# tractor_1v2.net
KiCad netlist of a schematic drawn in EAGLE
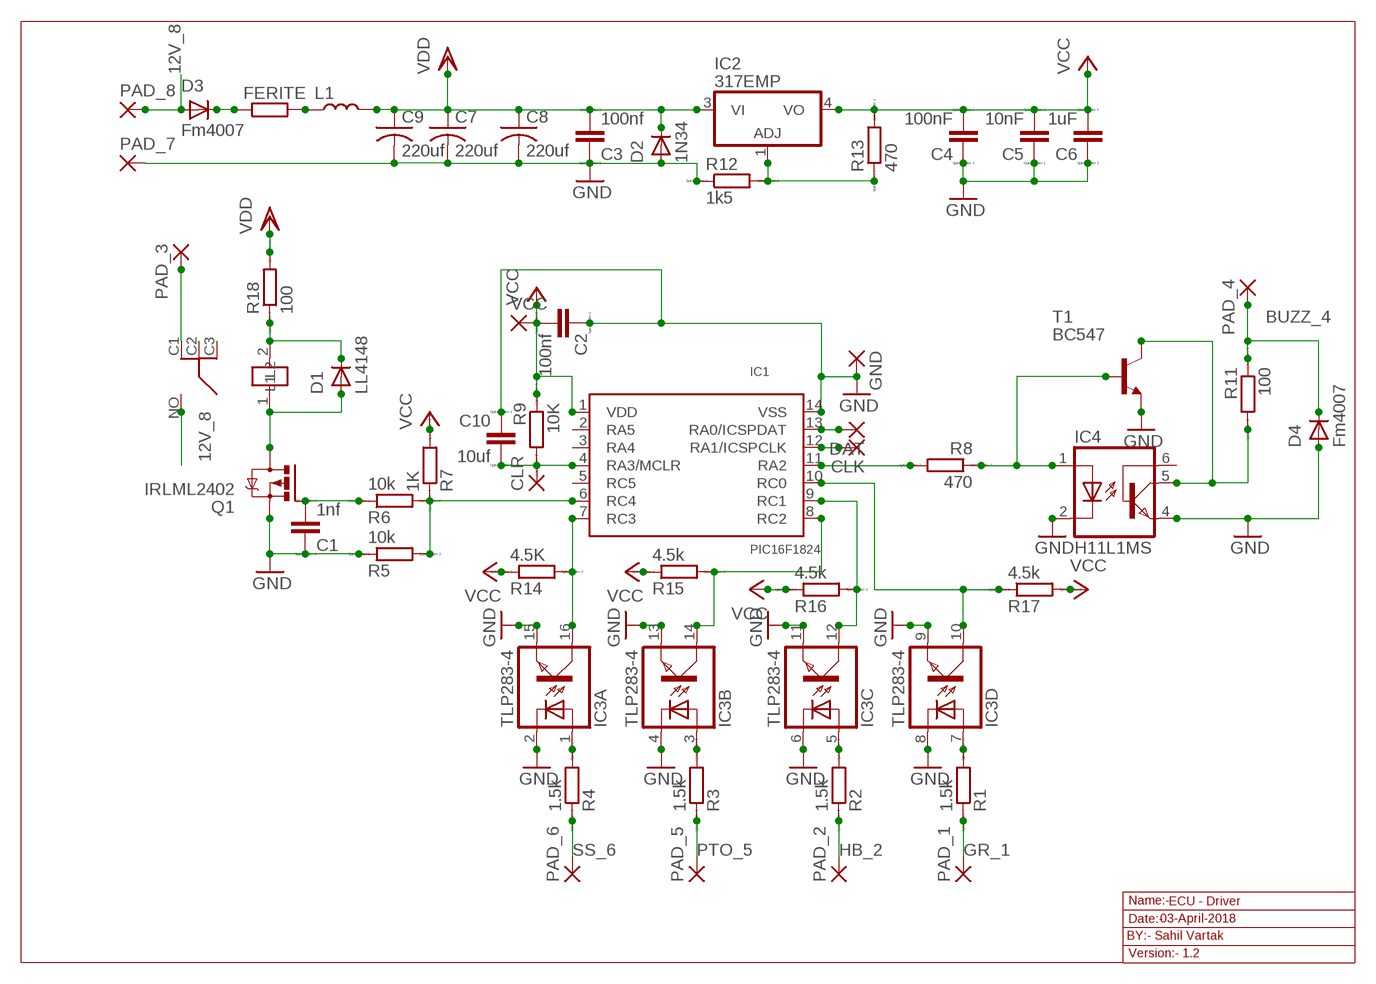
[diagram p0: schematic, sheet 1]

(export (version "E")
  (design (tool "Eeschema 10.0.6"))
  (components
    (comp (ref "C1")
      (value "1nf")
      (footprint "eagle-import:C0603")
      (libsource (lib "eagle-import") (part "CC0603"))
    )
    (comp (ref "C2")
      (value "100nf")
      (footprint "eagle-import:C0603")
      (libsource (lib "eagle-import") (part "CC0603"))
    )
    (comp (ref "C3")
      (value "100nf")
      (footprint "eagle-import:C0603")
      (libsource (lib "eagle-import") (part "CC0603"))
    )
    (comp (ref "C4")
      (value "100nF")
      (footprint "eagle-import:C0603")
      (libsource (lib "eagle-import") (part "CC0603"))
    )
    (comp (ref "C5")
      (value "10nF")
      (footprint "eagle-import:C0603")
      (libsource (lib "eagle-import") (part "CC0603"))
    )
    (comp (ref "C6")
      (value "1uF")
      (footprint "eagle-import:C0603")
      (libsource (lib "eagle-import") (part "CC0603"))
    )
    (comp (ref "C7")
      (value "220uf")
      (footprint "eagle-import:C025-025X050")
      (libsource (lib "eagle-import") (part "C-US025-025X050"))
    )
    (comp (ref "C8")
      (value "220uf")
      (footprint "eagle-import:C025-025X050")
      (libsource (lib "eagle-import") (part "C-US025-025X050"))
    )
    (comp (ref "C9")
      (value "220uf")
      (footprint "eagle-import:C025-025X050")
      (libsource (lib "eagle-import") (part "C-US025-025X050"))
    )
    (comp (ref "C10")
      (value "10uf")
      (footprint "eagle-import:C0603")
      (libsource (lib "eagle-import") (part "CC0603"))
    )
    (comp (ref "CLK")
      (value "1,6/0,8")
      (footprint "eagle-import:1,6_0,8")
      (libsource (lib "eagle-import") (part "1,6/0,8"))
    )
    (comp (ref "CLR")
      (value "1,6/0,8")
      (footprint "eagle-import:1,6_0,8")
      (libsource (lib "eagle-import") (part "1,6/0,8"))
    )
    (comp (ref "D1")
      (value "LL4148")
      (footprint "eagle-import:SMA-DO214AC")
      (libsource (lib "eagle-import") (part "GF1"))
    )
    (comp (ref "D2")
      (value "1N34")
      (footprint "eagle-import:SMA-DO214AC")
      (libsource (lib "eagle-import") (part "GF1"))
    )
    (comp (ref "D3")
      (value "Fm4007")
      (footprint "eagle-import:SMA-DO214AC")
      (libsource (lib "eagle-import") (part "GF1"))
    )
    (comp (ref "D4")
      (value "Fm4007")
      (footprint "eagle-import:SMA-DO214AC")
      (libsource (lib "eagle-import") (part "GF1"))
    )
    (comp (ref "DAT")
      (value "1,6/0,8")
      (footprint "eagle-import:1,6_0,8")
      (libsource (lib "eagle-import") (part "1,6/0,8"))
    )
    (comp (ref "FERITE")
      (value "R-EU_R0603")
      (footprint "eagle-import:R0603")
      (libsource (lib "eagle-import") (part "R-EU_R0603"))
    )
    (comp (ref "GND")
      (value "1,6/0,8")
      (footprint "eagle-import:1,6_0,8")
      (libsource (lib "eagle-import") (part "1,6/0,8"))
    )
    (comp (ref "IC1")
      (value "PIC16F1824")
      (footprint "eagle-import:SO-14")
      (libsource (lib "eagle-import") (part "PIC16F1824"))
    )
    (comp (ref "IC2")
      (value "317EMP")
      (footprint "eagle-import:SOT223")
      (libsource (lib "eagle-import") (part "317EMP"))
    )
    (comp (ref "IC3")
      (value "TLP283-4")
      (footprint "eagle-import:MINI-FLAT-16")
      (libsource (lib "eagle-import") (part "TLP283-4"))
    )
    (comp (ref "IC4")
      (value "H11L1MS")
      (footprint "eagle-import:DIL6-SMD")
      (libsource (lib "eagle-import") (part "H11LMS1"))
    )
    (comp (ref "K2")
      (value "RL703")
      (footprint "eagle-import:RL703")
      (libsource (lib "eagle-import") (part "RL703"))
    )
    (comp (ref "L1")
      (value "R-US_WSC2515")
      (footprint "eagle-import:WSC2515")
      (libsource (lib "eagle-import") (part "R-US_WSC2515"))
    )
    (comp (ref "PAD_1")
      (value "2,54/1,1")
      (footprint "eagle-import:2,54_1,1")
      (libsource (lib "eagle-import") (part "2,54/1,1"))
    )
    (comp (ref "PAD_2")
      (value "2,54/1,1")
      (footprint "eagle-import:2,54_1,1")
      (libsource (lib "eagle-import") (part "2,54/1,1"))
    )
    (comp (ref "PAD_3")
      (value "2,54/1,1")
      (footprint "eagle-import:2,54_1,1")
      (libsource (lib "eagle-import") (part "2,54/1,1"))
    )
    (comp (ref "PAD_4")
      (value "2,54/1,1")
      (footprint "eagle-import:2,54_1,1")
      (libsource (lib "eagle-import") (part "2,54/1,1"))
    )
    (comp (ref "PAD_5")
      (value "2,54/1,1")
      (footprint "eagle-import:2,54_1,1")
      (libsource (lib "eagle-import") (part "2,54/1,1"))
    )
    (comp (ref "PAD_6")
      (value "2,54/1,1")
      (footprint "eagle-import:2,54_1,1")
      (libsource (lib "eagle-import") (part "2,54/1,1"))
    )
    (comp (ref "PAD_7")
      (value "2,54/1,1")
      (footprint "eagle-import:2,54_1,1")
      (libsource (lib "eagle-import") (part "2,54/1,1"))
    )
    (comp (ref "PAD_8")
      (value "2,54/1,1")
      (footprint "eagle-import:2,54_1,1")
      (libsource (lib "eagle-import") (part "2,54/1,1"))
    )
    (comp (ref "Q1")
      (value "IRLML2402")
      (footprint "eagle-import:MICRO3")
      (libsource (lib "eagle-import") (part "IRLML5203"))
    )
    (comp (ref "R1")
      (value "1.5k")
      (footprint "eagle-import:R0603")
      (libsource (lib "eagle-import") (part "RR0603"))
    )
    (comp (ref "R2")
      (value "1.5k")
      (footprint "eagle-import:R0603")
      (libsource (lib "eagle-import") (part "RR0603"))
    )
    (comp (ref "R3")
      (value "1.5k")
      (footprint "eagle-import:R0603")
      (libsource (lib "eagle-import") (part "RR0603"))
    )
    (comp (ref "R4")
      (value "1.5k")
      (footprint "eagle-import:R0603")
      (libsource (lib "eagle-import") (part "RR0603"))
    )
    (comp (ref "R5")
      (value "10k")
      (footprint "eagle-import:R0603")
      (libsource (lib "eagle-import") (part "RR0603"))
    )
    (comp (ref "R6")
      (value "10k")
      (footprint "eagle-import:R0603")
      (libsource (lib "eagle-import") (part "RR0603"))
    )
    (comp (ref "R7")
      (value "1K")
      (footprint "eagle-import:R0603")
      (libsource (lib "eagle-import") (part "RR0603"))
    )
    (comp (ref "R8")
      (value "470")
      (footprint "eagle-import:R0603")
      (libsource (lib "eagle-import") (part "RR0603"))
    )
    (comp (ref "R9")
      (value "10K")
      (footprint "eagle-import:R0603")
      (libsource (lib "eagle-import") (part "RR0603"))
    )
    (comp (ref "R11")
      (value "100")
      (footprint "eagle-import:R0603")
      (libsource (lib "eagle-import") (part "RR0603"))
    )
    (comp (ref "R12")
      (value "1k5")
      (footprint "eagle-import:R0603")
      (libsource (lib "eagle-import") (part "RR0603"))
    )
    (comp (ref "R13")
      (value "470")
      (footprint "eagle-import:R0603")
      (libsource (lib "eagle-import") (part "RR0603"))
    )
    (comp (ref "R14")
      (value "4.5K")
      (footprint "eagle-import:R0603")
      (libsource (lib "eagle-import") (part "RR0603"))
    )
    (comp (ref "R15")
      (value "4.5k")
      (footprint "eagle-import:R0603")
      (libsource (lib "eagle-import") (part "RR0603"))
    )
    (comp (ref "R16")
      (value "4.5k")
      (footprint "eagle-import:R0603")
      (libsource (lib "eagle-import") (part "RR0603"))
    )
    (comp (ref "R17")
      (value "4.5k")
      (footprint "eagle-import:R0603")
      (libsource (lib "eagle-import") (part "RR0603"))
    )
    (comp (ref "R18")
      (value "100")
      (footprint "eagle-import:R0603")
      (libsource (lib "eagle-import") (part "RR0603"))
    )
    (comp (ref "T1")
      (value "BC547")
      (footprint "eagle-import:TO92")
      (libsource (lib "eagle-import") (part "BC547"))
    )
    (comp (ref "VCC")
      (value "1,6/0,8")
      (footprint "eagle-import:1,6_0,8")
      (libsource (lib "eagle-import") (part "1,6/0,8"))
    )
  )
  (nets
    (net (code "1") (name "/12V_8") (class "Default")
      (node (ref "D3") (pin "A") (pinfunction "A_A") (pintype "passive"))
      (node (ref "K2") (pin "NO") (pinfunction "NO_NO") (pintype "bidirectional"))
      (node (ref "PAD_8") (pin "1") (pinfunction "P_1") (pintype "passive"))
    )
    (net (code "2") (name "/BUZZ_4") (class "Default")
      (node (ref "D4") (pin "K") (pinfunction "C_K") (pintype "passive"))
      (node (ref "PAD_4") (pin "1") (pinfunction "P_1") (pintype "passive"))
      (node (ref "R11") (pin "1") (pinfunction "1_1") (pintype "passive"))
    )
    (net (code "3") (name "/GR_1") (class "Default")
      (node (ref "PAD_1") (pin "1") (pinfunction "P_1") (pintype "passive"))
      (node (ref "R1") (pin "1") (pinfunction "1_1") (pintype "passive"))
    )
    (net (code "4") (name "/HB_2") (class "Default")
      (node (ref "PAD_2") (pin "1") (pinfunction "P_1") (pintype "passive"))
      (node (ref "R2") (pin "1") (pinfunction "1_1") (pintype "passive"))
    )
    (net (code "5") (name "/PTO_5") (class "Default")
      (node (ref "PAD_5") (pin "1") (pinfunction "P_1") (pintype "passive"))
      (node (ref "R3") (pin "1") (pinfunction "1_1") (pintype "passive"))
    )
    (net (code "6") (name "/SS_6") (class "Default")
      (node (ref "PAD_6") (pin "1") (pinfunction "P_1") (pintype "passive"))
      (node (ref "R4") (pin "1") (pinfunction "1_1") (pintype "passive"))
    )
    (net (code "7") (name "GND") (class "Default")
      (node (ref "C1") (pin "1") (pinfunction "1_1") (pintype "passive"))
      (node (ref "C10") (pin "1") (pinfunction "1_1") (pintype "passive"))
      (node (ref "C2") (pin "1") (pinfunction "1_1") (pintype "passive"))
      (node (ref "C3") (pin "1") (pinfunction "1_1") (pintype "passive"))
      (node (ref "C4") (pin "1") (pinfunction "1_1") (pintype "passive"))
      (node (ref "C5") (pin "1") (pinfunction "1_1") (pintype "passive"))
      (node (ref "C6") (pin "1") (pinfunction "1_1") (pintype "passive"))
      (node (ref "C7") (pin "2") (pinfunction "2_2") (pintype "passive"))
      (node (ref "C8") (pin "2") (pinfunction "2_2") (pintype "passive"))
      (node (ref "C9") (pin "2") (pinfunction "2_2") (pintype "passive"))
      (node (ref "D2") (pin "A") (pinfunction "A_A") (pintype "passive"))
      (node (ref "D4") (pin "A") (pinfunction "A_A") (pintype "passive"))
      (node (ref "GND") (pin "1") (pinfunction "P_1") (pintype "passive"))
      (node (ref "IC1") (pin "14") (pinfunction "VSS_14") (pintype "bidirectional"))
      (node (ref "IC3") (pin "11") (pinfunction "EMIT_11") (pintype "passive"))
      (node (ref "IC3") (pin "13") (pinfunction "EMIT_13") (pintype "passive"))
      (node (ref "IC3") (pin "15") (pinfunction "EMIT_15") (pintype "passive"))
      (node (ref "IC3") (pin "2") (pinfunction "C_2") (pintype "passive"))
      (node (ref "IC3") (pin "4") (pinfunction "C_4") (pintype "passive"))
      (node (ref "IC3") (pin "6") (pinfunction "C_6") (pintype "passive"))
      (node (ref "IC3") (pin "8") (pinfunction "C_8") (pintype "passive"))
      (node (ref "IC3") (pin "9") (pinfunction "EMIT_9") (pintype "passive"))
      (node (ref "IC4") (pin "2") (pinfunction "C_2") (pintype "passive"))
      (node (ref "IC4") (pin "4") (pinfunction "EMI_4") (pintype "passive"))
      (node (ref "PAD_7") (pin "1") (pinfunction "P_1") (pintype "passive"))
      (node (ref "Q1") (pin "2") (pinfunction "S_2") (pintype "passive"))
      (node (ref "R12") (pin "1") (pinfunction "1_1") (pintype "passive"))
      (node (ref "R5") (pin "1") (pinfunction "1_1") (pintype "passive"))
      (node (ref "T1") (pin "1") (pinfunction "E_1") (pintype "passive"))
    )
    (net (code "8") (name "Net-(CLK-P)") (class "Default")
      (node (ref "CLK") (pin "1") (pinfunction "P_1") (pintype "passive"))
      (node (ref "IC1") (pin "12") (pinfunction "RA1/ICSPCLK_12") (pintype "bidirectional"))
    )
    (net (code "9") (name "Net-(CLR-P)") (class "Default")
      (node (ref "C10") (pin "2") (pinfunction "2_2") (pintype "passive"))
      (node (ref "CLR") (pin "1") (pinfunction "P_1") (pintype "passive"))
      (node (ref "IC1") (pin "4") (pinfunction "RA3/MCLR_4") (pintype "bidirectional"))
      (node (ref "R9") (pin "2") (pinfunction "2_2") (pintype "passive"))
    )
    (net (code "10") (name "Net-(D1-C)") (class "Default")
      (node (ref "D1") (pin "K") (pinfunction "C_K") (pintype "passive"))
      (node (ref "K2") (pin "2") (pinfunction "L1_2") (pintype "bidirectional"))
      (node (ref "R18") (pin "1") (pinfunction "1_1") (pintype "passive"))
    )
    (net (code "11") (name "Net-(D3-C)") (class "Default")
      (node (ref "D3") (pin "K") (pinfunction "C_K") (pintype "passive"))
      (node (ref "FERITE") (pin "1") (pinfunction "1_1") (pintype "passive"))
    )
    (net (code "12") (name "Net-(DAT-P)") (class "Default")
      (node (ref "DAT") (pin "1") (pinfunction "P_1") (pintype "passive"))
      (node (ref "IC1") (pin "13") (pinfunction "RA0/ICSPDAT_13") (pintype "bidirectional"))
    )
    (net (code "13") (name "Net-(FERITE-Pad2)") (class "Default")
      (node (ref "FERITE") (pin "2") (pinfunction "2_2") (pintype "passive"))
      (node (ref "L1") (pin "1") (pinfunction "1_1") (pintype "passive"))
    )
    (net (code "14") (name "Net-(IC1-RA2)") (class "Default")
      (node (ref "IC1") (pin "11") (pinfunction "RA2_11") (pintype "bidirectional"))
      (node (ref "R8") (pin "2") (pinfunction "2_2") (pintype "passive"))
    )
    (net (code "15") (name "Net-(IC1-RC0)") (class "Default")
      (node (ref "IC1") (pin "10") (pinfunction "RC0_10") (pintype "bidirectional"))
      (node (ref "IC3") (pin "10") (pinfunction "COL_10") (pintype "passive"))
      (node (ref "R17") (pin "1") (pinfunction "1_1") (pintype "passive"))
    )
    (net (code "16") (name "Net-(IC1-RC1)") (class "Default")
      (node (ref "IC1") (pin "9") (pinfunction "RC1_9") (pintype "bidirectional"))
      (node (ref "IC3") (pin "12") (pinfunction "COL_12") (pintype "passive"))
      (node (ref "R16") (pin "2") (pinfunction "2_2") (pintype "passive"))
    )
    (net (code "17") (name "Net-(IC1-RC2)") (class "Default")
      (node (ref "IC1") (pin "8") (pinfunction "RC2_8") (pintype "bidirectional"))
      (node (ref "IC3") (pin "14") (pinfunction "COL_14") (pintype "passive"))
      (node (ref "R15") (pin "2") (pinfunction "2_2") (pintype "passive"))
    )
    (net (code "18") (name "Net-(IC1-RC3)") (class "Default")
      (node (ref "IC1") (pin "7") (pinfunction "RC3_7") (pintype "bidirectional"))
      (node (ref "IC3") (pin "16") (pinfunction "COL_16") (pintype "passive"))
      (node (ref "R14") (pin "2") (pinfunction "2_2") (pintype "passive"))
    )
    (net (code "19") (name "Net-(IC1-RC4)") (class "Default")
      (node (ref "IC1") (pin "6") (pinfunction "RC4_6") (pintype "bidirectional"))
      (node (ref "R5") (pin "2") (pinfunction "2_2") (pintype "passive"))
      (node (ref "R6") (pin "2") (pinfunction "2_2") (pintype "passive"))
      (node (ref "R7") (pin "1") (pinfunction "1_1") (pintype "passive"))
    )
    (net (code "20") (name "Net-(IC2-ADJ)") (class "Default")
      (node (ref "IC2") (pin "1") (pinfunction "ADJ_1") (pintype "input"))
      (node (ref "R12") (pin "2") (pinfunction "2_2") (pintype "passive"))
      (node (ref "R13") (pin "1") (pinfunction "1_1") (pintype "passive"))
    )
    (net (code "21") (name "Net-(IC3A-A)") (class "Default")
      (node (ref "IC3") (pin "1") (pinfunction "A_1") (pintype "passive"))
      (node (ref "R4") (pin "2") (pinfunction "2_2") (pintype "passive"))
    )
    (net (code "22") (name "Net-(IC3B-A)") (class "Default")
      (node (ref "IC3") (pin "3") (pinfunction "A_3") (pintype "passive"))
      (node (ref "R3") (pin "2") (pinfunction "2_2") (pintype "passive"))
    )
    (net (code "23") (name "Net-(IC3C-A)") (class "Default")
      (node (ref "IC3") (pin "5") (pinfunction "A_5") (pintype "passive"))
      (node (ref "R2") (pin "2") (pinfunction "2_2") (pintype "passive"))
    )
    (net (code "24") (name "Net-(IC3D-A)") (class "Default")
      (node (ref "IC3") (pin "7") (pinfunction "A_7") (pintype "passive"))
      (node (ref "R1") (pin "2") (pinfunction "2_2") (pintype "passive"))
    )
    (net (code "25") (name "Net-(IC4-A)") (class "Default")
      (node (ref "IC4") (pin "1") (pinfunction "A_1") (pintype "passive"))
      (node (ref "R8") (pin "1") (pinfunction "1_1") (pintype "passive"))
      (node (ref "T1") (pin "2") (pinfunction "B_2") (pintype "passive"))
    )
    (net (code "26") (name "Net-(IC4-COL)") (class "Default")
      (node (ref "IC4") (pin "5") (pinfunction "COL_5") (pintype "passive"))
      (node (ref "R11") (pin "2") (pinfunction "2_2") (pintype "passive"))
      (node (ref "T1") (pin "3") (pinfunction "C_3") (pintype "passive"))
    )
    (net (code "27") (name "Net-(K2-L2)") (class "Default")
      (node (ref "D1") (pin "A") (pinfunction "A_A") (pintype "passive"))
      (node (ref "K2") (pin "1") (pinfunction "L2_1") (pintype "bidirectional"))
      (node (ref "Q1") (pin "3") (pinfunction "D_3") (pintype "passive"))
    )
    (net (code "28") (name "Net-(PAD_3-P)") (class "Default")
      (node (ref "K2") (pin "C1") (pinfunction "C1_C1") (pintype "bidirectional"))
      (node (ref "PAD_3") (pin "1") (pinfunction "P_1") (pintype "passive"))
    )
    (net (code "29") (name "Net-(Q1-G)") (class "Default")
      (node (ref "C1") (pin "2") (pinfunction "2_2") (pintype "passive"))
      (node (ref "Q1") (pin "1") (pinfunction "G_1") (pintype "passive"))
      (node (ref "R6") (pin "1") (pinfunction "1_1") (pintype "passive"))
    )
    (net (code "30") (name "VCC") (class "Default")
      (node (ref "C2") (pin "2") (pinfunction "2_2") (pintype "passive"))
      (node (ref "C4") (pin "2") (pinfunction "2_2") (pintype "passive"))
      (node (ref "C5") (pin "2") (pinfunction "2_2") (pintype "passive"))
      (node (ref "C6") (pin "2") (pinfunction "2_2") (pintype "passive"))
      (node (ref "IC1") (pin "1") (pinfunction "VDD_1") (pintype "bidirectional"))
      (node (ref "IC2") (pin "4") (pinfunction "VO_4") (pintype "passive"))
      (node (ref "R13") (pin "2") (pinfunction "2_2") (pintype "passive"))
      (node (ref "R14") (pin "1") (pinfunction "1_1") (pintype "passive"))
      (node (ref "R15") (pin "1") (pinfunction "1_1") (pintype "passive"))
      (node (ref "R16") (pin "1") (pinfunction "1_1") (pintype "passive"))
      (node (ref "R17") (pin "2") (pinfunction "2_2") (pintype "passive"))
      (node (ref "R7") (pin "2") (pinfunction "2_2") (pintype "passive"))
      (node (ref "R9") (pin "1") (pinfunction "1_1") (pintype "passive"))
      (node (ref "VCC") (pin "1") (pinfunction "P_1") (pintype "passive"))
    )
    (net (code "31") (name "VDD") (class "Default")
      (node (ref "C3") (pin "2") (pinfunction "2_2") (pintype "passive"))
      (node (ref "C7") (pin "1") (pinfunction "1_1") (pintype "passive"))
      (node (ref "C8") (pin "1") (pinfunction "1_1") (pintype "passive"))
      (node (ref "C9") (pin "1") (pinfunction "1_1") (pintype "passive"))
      (node (ref "D2") (pin "K") (pinfunction "C_K") (pintype "passive"))
      (node (ref "IC2") (pin "3") (pinfunction "VI_3") (pintype "input"))
      (node (ref "L1") (pin "2") (pinfunction "2_2") (pintype "passive"))
      (node (ref "R18") (pin "2") (pinfunction "2_2") (pintype "passive"))
    )
    (net (code "32") (name "unconnected-(IC1-RA4-Pad3)") (class "Default")
      (node (ref "IC1") (pin "3") (pinfunction "RA4_3") (pintype "bidirectional"))
    )
    (net (code "33") (name "unconnected-(IC1-RA5-Pad2)") (class "Default")
      (node (ref "IC1") (pin "2") (pinfunction "RA5_2") (pintype "bidirectional"))
    )
    (net (code "34") (name "unconnected-(IC1-RC5-Pad5)") (class "Default")
      (node (ref "IC1") (pin "5") (pinfunction "RC5_5") (pintype "bidirectional"))
    )
    (net (code "35") (name "unconnected-(IC4-BAS-Pad6)") (class "Default")
      (node (ref "IC4") (pin "6") (pinfunction "BAS_6") (pintype "passive"))
    )
    (net (code "36") (name "unconnected-(K2-PadC2)") (class "Default")
      (node (ref "K2") (pin "C2") (pinfunction "C2_C2") (pintype "bidirectional"))
    )
    (net (code "37") (name "unconnected-(K2-PadC3)") (class "Default")
      (node (ref "K2") (pin "C3") (pinfunction "C3_C3") (pintype "bidirectional"))
    )
  )
)
